# Sch_Add.net
KiCad netlist of a schematic drawn in Altium Designer
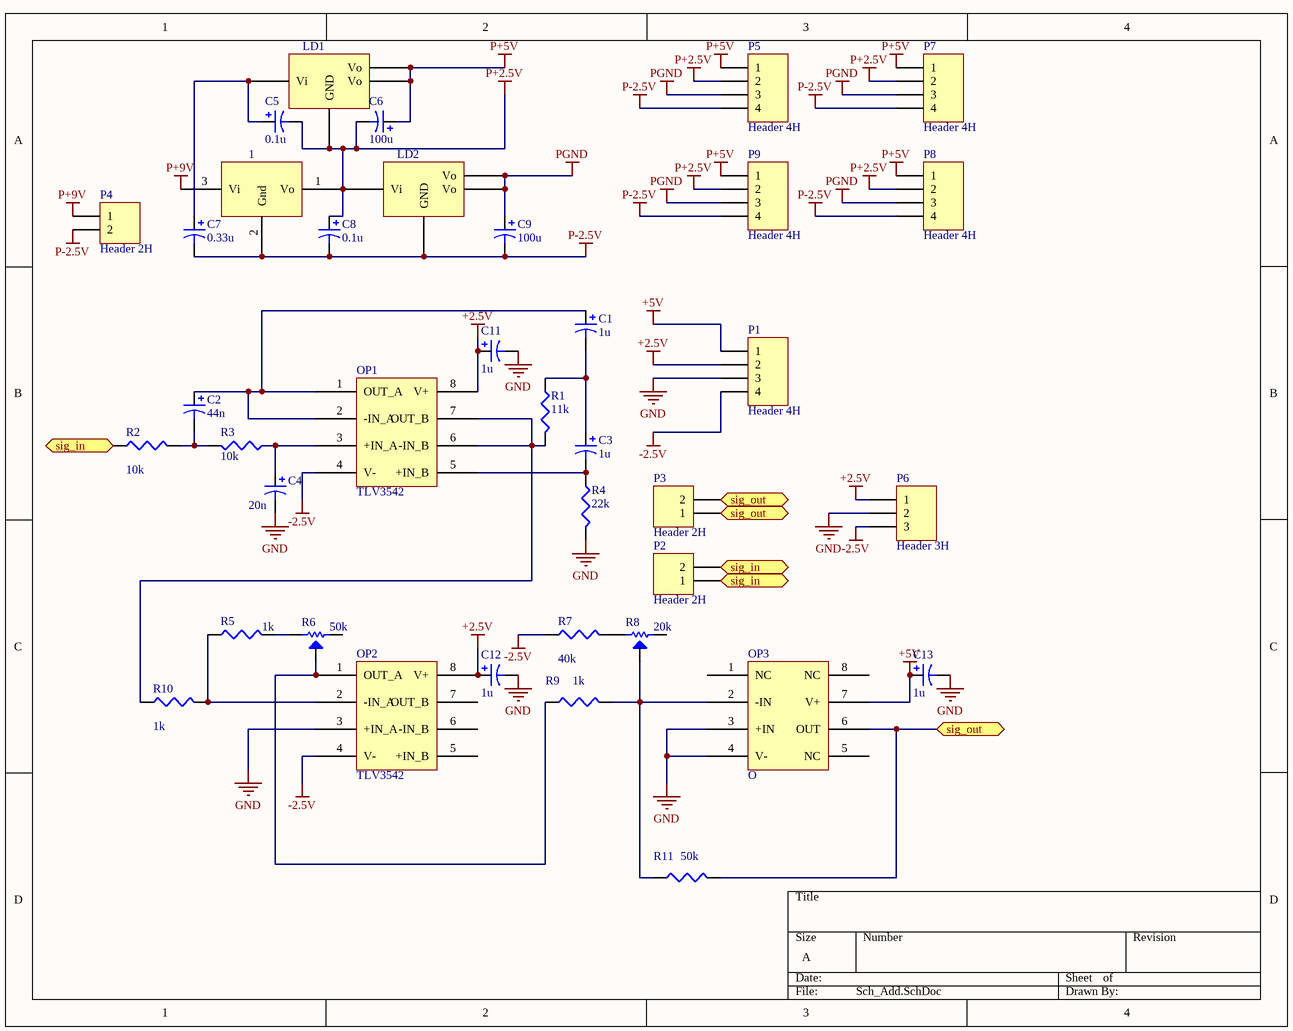
[diagram p0: Sch_Add.SchDoc]

(export (version "E")
  (design (tool "Eeschema 10.0.6"))
  (components
    (comp (ref "1") (value "7805") (footprint "TO-92") (libsource (lib "tlv3542") (part "7805")))
    (comp (ref "C1")
      (value "1u")
      (footprint "C0805")
      (description "Polarized Capacitor (Surface Mount)")
      (fields (field (name "Comment") "Cap Pol3") (field (name "PUBLISHER") "Altium Limited"))
      (libsource (lib "Miscellaneous Devices") (part "Cap Pol3"))
    )
    (comp (ref "C2")
      (value "44n")
      (footprint "C0805")
      (description "Polarized Capacitor (Surface Mount)")
      (fields (field (name "Comment") "Cap Pol3") (field (name "PUBLISHER") "Altium Limited"))
      (libsource (lib "Miscellaneous Devices") (part "Cap Pol3"))
    )
    (comp (ref "C3")
      (value "1u")
      (footprint "C0805")
      (description "Polarized Capacitor (Surface Mount)")
      (fields (field (name "Comment") "Cap Pol3") (field (name "PUBLISHER") "Altium Limited"))
      (libsource (lib "Miscellaneous Devices") (part "Cap Pol3"))
    )
    (comp (ref "C4")
      (value "20n")
      (footprint "C0805")
      (description "Polarized Capacitor (Surface Mount)")
      (fields (field (name "Comment") "Cap Pol3") (field (name "PUBLISHER") "Altium Limited"))
      (libsource (lib "Miscellaneous Devices") (part "Cap Pol3"))
    )
    (comp (ref "C5")
      (value "0.1u")
      (footprint "C0805")
      (description "Polarized Capacitor (Surface Mount)")
      (fields (field (name "Comment") "Cap Pol3") (field (name "PUBLISHER") "Altium Limited"))
      (libsource (lib "Miscellaneous Devices") (part "Cap Pol3"))
    )
    (comp (ref "C6")
      (value "100u")
      (footprint "C0805")
      (description "Polarized Capacitor (Surface Mount)")
      (fields (field (name "Comment") "Cap Pol3") (field (name "PUBLISHER") "Altium Limited"))
      (libsource (lib "Miscellaneous Devices") (part "Cap Pol3"))
    )
    (comp (ref "C7")
      (value "0.33u")
      (footprint "C0805")
      (description "Polarized Capacitor (Surface Mount)")
      (fields (field (name "Comment") "Cap Pol3") (field (name "PUBLISHER") "Altium Limited"))
      (libsource (lib "Miscellaneous Devices") (part "Cap Pol3"))
    )
    (comp (ref "C8")
      (value "0.1u")
      (footprint "C0805")
      (description "Polarized Capacitor (Surface Mount)")
      (fields (field (name "Comment") "Cap Pol3") (field (name "PUBLISHER") "Altium Limited"))
      (libsource (lib "Miscellaneous Devices") (part "Cap Pol3"))
    )
    (comp (ref "C9")
      (value "100u")
      (footprint "C0805")
      (description "Polarized Capacitor (Surface Mount)")
      (fields (field (name "Comment") "Cap Pol3") (field (name "PUBLISHER") "Altium Limited"))
      (libsource (lib "Miscellaneous Devices") (part "Cap Pol3"))
    )
    (comp (ref "C11")
      (value "1u")
      (footprint "C0805")
      (description "Polarized Capacitor (Surface Mount)")
      (fields (field (name "Comment") "Cap Pol3") (field (name "PUBLISHER") "Altium Limited"))
      (libsource (lib "Miscellaneous Devices") (part "Cap Pol3"))
    )
    (comp (ref "C12")
      (value "1u")
      (footprint "C0805")
      (description "Polarized Capacitor (Surface Mount)")
      (fields (field (name "Comment") "Cap Pol3") (field (name "PUBLISHER") "Altium Limited"))
      (libsource (lib "Miscellaneous Devices") (part "Cap Pol3"))
    )
    (comp (ref "C13")
      (value "1u")
      (footprint "C0805")
      (description "Polarized Capacitor (Surface Mount)")
      (fields (field (name "Comment") "Cap Pol3") (field (name "PUBLISHER") "Altium Limited"))
      (libsource (lib "Miscellaneous Devices") (part "Cap Pol3"))
    )
    (comp (ref "LD1")
      (value "LD1117")
      (footprint "SOT230P700X180-4N")
      (libsource (lib "tlv3542") (part "LD1117"))
    )
    (comp (ref "LD2")
      (value "LD1117")
      (footprint "SOT230P700X180-4N")
      (libsource (lib "tlv3542") (part "LD1117"))
    )
    (comp (ref "OP1")
      (value "TLV3542")
      (footprint "SOIC127P600X175-8N")
      (libsource (lib "tlv3542") (part "TLV3542"))
    )
    (comp (ref "OP2")
      (value "TLV3542")
      (footprint "SOIC127P600X175-8N")
      (libsource (lib "tlv3542") (part "TLV3542"))
    )
    (comp (ref "OP3")
      (value "O")
      (footprint "SOIC127P600X175-8N")
      (libsource (lib "tlv3542") (part "OPA388IDR"))
    )
    (comp (ref "P1")
      (value "Header 4H")
      (footprint "HDR1X4H")
      (description "Header, 4-Pin, Right Angle")
      (fields (field (name "PUBLISHER") "Altium Limited"))
      (libsource (lib "Miscellaneous Connectors") (part "Header 4H"))
    )
    (comp (ref "P2")
      (value "Header 2H")
      (footprint "HDR1X2H")
      (description "Header, 2-Pin, Right Angle")
      (fields (field (name "PUBLISHER") "Altium Limited"))
      (libsource (lib "Miscellaneous Connectors") (part "Header 2H"))
    )
    (comp (ref "P3")
      (value "Header 2H")
      (footprint "HDR1X2H")
      (description "Header, 2-Pin, Right Angle")
      (fields (field (name "PUBLISHER") "Altium Limited"))
      (libsource (lib "Miscellaneous Connectors") (part "Header 2H"))
    )
    (comp (ref "P4")
      (value "Header 2H")
      (footprint "HDR1X2H")
      (description "Header, 2-Pin, Right Angle")
      (fields (field (name "PUBLISHER") "Altium Limited"))
      (libsource (lib "") (part "Header 2H_1"))
    )
    (comp (ref "P5")
      (value "Header 4H")
      (footprint "HDR1X4H")
      (description "Header, 4-Pin, Right Angle")
      (fields (field (name "PUBLISHER") "Altium Limited"))
      (libsource (lib "Miscellaneous Connectors") (part "Header 4H"))
    )
    (comp (ref "P6")
      (value "Header 3H")
      (footprint "HDR1X3H")
      (description "Header, 3-Pin, Right Angle")
      (fields (field (name "PUBLISHER") "Altium Limited"))
      (libsource (lib "Miscellaneous Connectors") (part "Header 3H"))
    )
    (comp (ref "P7")
      (value "Header 4H")
      (footprint "HDR1X4H")
      (description "Header, 4-Pin, Right Angle")
      (fields (field (name "PUBLISHER") "Altium Limited"))
      (libsource (lib "Miscellaneous Connectors") (part "Header 4H"))
    )
    (comp (ref "P8")
      (value "Header 4H")
      (footprint "HDR1X4H")
      (description "Header, 4-Pin, Right Angle")
      (fields (field (name "PUBLISHER") "Altium Limited"))
      (libsource (lib "Miscellaneous Connectors") (part "Header 4H"))
    )
    (comp (ref "P9")
      (value "Header 4H")
      (footprint "HDR1X4H")
      (description "Header, 4-Pin, Right Angle")
      (fields (field (name "PUBLISHER") "Altium Limited"))
      (libsource (lib "Miscellaneous Connectors") (part "Header 4H"))
    )
    (comp (ref "R1")
      (value "11k")
      (footprint "J1-0603")
      (description "Resistor")
      (fields (field (name "Comment") "Res3") (field (name "PUBLISHER") "Altium Limited"))
      (libsource (lib "Miscellaneous Devices") (part "Res3"))
    )
    (comp (ref "R2")
      (value "10k")
      (footprint "J1-0603")
      (description "Resistor")
      (fields (field (name "Comment") "Res3") (field (name "PUBLISHER") "Altium Limited"))
      (libsource (lib "Miscellaneous Devices") (part "Res3"))
    )
    (comp (ref "R3")
      (value "10k")
      (footprint "J1-0603")
      (description "Resistor")
      (fields (field (name "Comment") "Res3") (field (name "PUBLISHER") "Altium Limited"))
      (libsource (lib "Miscellaneous Devices") (part "Res3"))
    )
    (comp (ref "R4")
      (value "22k")
      (footprint "J1-0603")
      (description "Resistor")
      (fields (field (name "Comment") "Res3") (field (name "PUBLISHER") "Altium Limited"))
      (libsource (lib "Miscellaneous Devices") (part "Res3"))
    )
    (comp (ref "R5")
      (value "1k")
      (footprint "J1-0603")
      (description "Resistor")
      (fields (field (name "Comment") "Res3") (field (name "PUBLISHER") "Altium Limited"))
      (libsource (lib "Miscellaneous Devices") (part "Res3"))
    )
    (comp (ref "R6")
      (value "50k")
      (footprint "3362P")
      (fields (field (name "Comment") "5"))
      (libsource (lib "tlv3542") (part "Res_3362P"))
    )
    (comp (ref "R7")
      (value "40k")
      (footprint "J1-0603")
      (description "Resistor")
      (fields (field (name "Comment") "Res3") (field (name "PUBLISHER") "Altium Limited"))
      (libsource (lib "Miscellaneous Devices") (part "Res3"))
    )
    (comp (ref "R8")
      (value "20k")
      (footprint "3362P")
      (fields (field (name "Comment") "2"))
      (libsource (lib "tlv3542") (part "Res_3362P"))
    )
    (comp (ref "R9")
      (value "1k")
      (footprint "J1-0603")
      (description "Resistor")
      (fields (field (name "Comment") "Res3") (field (name "PUBLISHER") "Altium Limited"))
      (libsource (lib "Miscellaneous Devices") (part "Res3"))
    )
    (comp (ref "R10")
      (value "1k")
      (footprint "J1-0603")
      (description "Resistor")
      (fields (field (name "Comment") "Res3") (field (name "PUBLISHER") "Altium Limited"))
      (libsource (lib "Miscellaneous Devices") (part "Res3"))
    )
    (comp (ref "R11")
      (value "50k")
      (footprint "J1-0603")
      (description "Resistor")
      (fields (field (name "Comment") "Res3") (field (name "PUBLISHER") "Altium Limited"))
      (libsource (lib "Miscellaneous Devices") (part "Res3"))
    )
  )
  (nets
    (net (code "1") (name "+2.5V") (class "Default")
      (node (ref "C11") (pin "1") (pinfunction "1_1") (pintype "passive"))
      (node (ref "C12") (pin "1") (pinfunction "1_1") (pintype "passive"))
      (node (ref "OP1") (pin "8") (pinfunction "V+_8") (pintype "passive"))
      (node (ref "OP2") (pin "8") (pinfunction "V+_8") (pintype "passive"))
      (node (ref "P1") (pin "2") (pinfunction "2_2") (pintype "passive"))
      (node (ref "P6") (pin "1") (pinfunction "1_1") (pintype "passive"))
    )
    (net (code "2") (name "+5V") (class "Default")
      (node (ref "C13") (pin "1") (pinfunction "1_1") (pintype "passive"))
      (node (ref "OP3") (pin "7") (pinfunction "V+_7") (pintype "passive"))
      (node (ref "P1") (pin "1") (pinfunction "1_1") (pintype "passive"))
    )
    (net (code "3") (name "-2.5V") (class "Default")
      (node (ref "OP1") (pin "4") (pinfunction "V-_4") (pintype "passive"))
      (node (ref "OP2") (pin "4") (pinfunction "V-_4") (pintype "passive"))
      (node (ref "P1") (pin "4") (pinfunction "4_4") (pintype "passive"))
      (node (ref "P6") (pin "3") (pinfunction "3_3") (pintype "passive"))
      (node (ref "R7") (pin "1") (pinfunction "1_1") (pintype "passive"))
    )
    (net (code "4") (name "/sig_in") (class "Default")
      (node (ref "P2") (pin "1") (pinfunction "1_1") (pintype "passive"))
      (node (ref "P2") (pin "2") (pinfunction "2_2") (pintype "passive"))
      (node (ref "R2") (pin "1") (pinfunction "1_1") (pintype "passive"))
    )
    (net (code "5") (name "/sig_out") (class "Default")
      (node (ref "OP3") (pin "6") (pinfunction "OUT_6") (pintype "passive"))
      (node (ref "P3") (pin "1") (pinfunction "1_1") (pintype "passive"))
      (node (ref "P3") (pin "2") (pinfunction "2_2") (pintype "passive"))
      (node (ref "R11") (pin "2") (pinfunction "2_2") (pintype "passive"))
    )
    (net (code "6") (name "GND") (class "Default")
      (node (ref "C11") (pin "2") (pinfunction "2_2") (pintype "passive"))
      (node (ref "C12") (pin "2") (pinfunction "2_2") (pintype "passive"))
      (node (ref "C13") (pin "2") (pinfunction "2_2") (pintype "passive"))
      (node (ref "C4") (pin "2") (pinfunction "2_2") (pintype "passive"))
      (node (ref "OP2") (pin "3") (pinfunction "+IN_A_3") (pintype "passive"))
      (node (ref "OP3") (pin "3") (pinfunction "+IN_3") (pintype "passive"))
      (node (ref "OP3") (pin "4") (pinfunction "V-_4") (pintype "passive"))
      (node (ref "P1") (pin "3") (pinfunction "3_3") (pintype "passive"))
      (node (ref "P6") (pin "2") (pinfunction "2_2") (pintype "passive"))
      (node (ref "R4") (pin "2") (pinfunction "2_2") (pintype "passive"))
    )
    (net (code "7") (name "Net-(C1-Pad2)") (class "Default")
      (node (ref "C1") (pin "2") (pinfunction "2_2") (pintype "passive"))
      (node (ref "C3") (pin "1") (pinfunction "1_1") (pintype "passive"))
      (node (ref "R1") (pin "1") (pinfunction "1_1") (pintype "passive"))
    )
    (net (code "8") (name "Net-(C2-Pad2)") (class "Default")
      (node (ref "C2") (pin "2") (pinfunction "2_2") (pintype "passive"))
      (node (ref "R2") (pin "2") (pinfunction "2_2") (pintype "passive"))
      (node (ref "R3") (pin "2") (pinfunction "2_2") (pintype "passive"))
    )
    (net (code "9") (name "Net-(LD1-Vi)") (class "Default")
      (node (ref "C5") (pin "1") (pinfunction "1_1") (pintype "passive"))
      (node (ref "C7") (pin "1") (pinfunction "1_1") (pintype "passive"))
      (node (ref "LD1") (pin "3") (pinfunction "Vi_3") (pintype "passive"))
    )
    (net (code "10") (name "Net-(OP1-+IN_A)") (class "Default")
      (node (ref "C4") (pin "1") (pinfunction "1_1") (pintype "passive"))
      (node (ref "OP1") (pin "3") (pinfunction "+IN_A_3") (pintype "passive"))
      (node (ref "R3") (pin "1") (pinfunction "1_1") (pintype "passive"))
    )
    (net (code "11") (name "Net-(OP1-+IN_B)") (class "Default")
      (node (ref "C3") (pin "2") (pinfunction "2_2") (pintype "passive"))
      (node (ref "OP1") (pin "5") (pinfunction "+IN_B_5") (pintype "passive"))
      (node (ref "R4") (pin "1") (pinfunction "1_1") (pintype "passive"))
    )
    (net (code "12") (name "Net-(OP1--IN_A)") (class "Default")
      (node (ref "C1") (pin "1") (pinfunction "1_1") (pintype "passive"))
      (node (ref "C2") (pin "1") (pinfunction "1_1") (pintype "passive"))
      (node (ref "OP1") (pin "1") (pinfunction "OUT_A_1") (pintype "passive"))
      (node (ref "OP1") (pin "2") (pinfunction "-IN_A_2") (pintype "passive"))
    )
    (net (code "13") (name "Net-(OP1--IN_B)") (class "Default")
      (node (ref "OP1") (pin "6") (pinfunction "-IN_B_6") (pintype "passive"))
      (node (ref "OP1") (pin "7") (pinfunction "OUT_B_7") (pintype "passive"))
      (node (ref "R1") (pin "2") (pinfunction "2_2") (pintype "passive"))
      (node (ref "R10") (pin "1") (pinfunction "1_1") (pintype "passive"))
    )
    (net (code "14") (name "Net-(OP2--IN_A)") (class "Default")
      (node (ref "OP2") (pin "2") (pinfunction "-IN_A_2") (pintype "passive"))
      (node (ref "R10") (pin "2") (pinfunction "2_2") (pintype "passive"))
      (node (ref "R5") (pin "1") (pinfunction "1_1") (pintype "passive"))
    )
    (net (code "15") (name "Net-(OP2-OUT_A)") (class "Default")
      (node (ref "OP2") (pin "1") (pinfunction "OUT_A_1") (pintype "passive"))
      (node (ref "R6") (pin "3") (pinfunction "3_3") (pintype "passive"))
      (node (ref "R9") (pin "1") (pinfunction "1_1") (pintype "passive"))
    )
    (net (code "16") (name "Net-(OP3--IN)") (class "Default")
      (node (ref "OP3") (pin "2") (pinfunction "-IN_2") (pintype "passive"))
      (node (ref "R11") (pin "1") (pinfunction "1_1") (pintype "passive"))
      (node (ref "R8") (pin "3") (pinfunction "3_3") (pintype "passive"))
      (node (ref "R9") (pin "2") (pinfunction "2_2") (pintype "passive"))
    )
    (net (code "17") (name "Net-(R5-Pad2)") (class "Default")
      (node (ref "R5") (pin "2") (pinfunction "2_2") (pintype "passive"))
      (node (ref "R6") (pin "1") (pinfunction "1_1") (pintype "passive"))
    )
    (net (code "18") (name "Net-(R7-Pad2)") (class "Default")
      (node (ref "R7") (pin "2") (pinfunction "2_2") (pintype "passive"))
      (node (ref "R8") (pin "1") (pinfunction "1_1") (pintype "passive"))
    )
    (net (code "19") (name "P+2.5V") (class "Default")
      (node (ref "1") (pin "1") (pinfunction "Vo_1") (pintype "passive"))
      (node (ref "C5") (pin "2") (pinfunction "2_2") (pintype "passive"))
      (node (ref "C6") (pin "2") (pinfunction "2_2") (pintype "passive"))
      (node (ref "C8") (pin "1") (pinfunction "1_1") (pintype "passive"))
      (node (ref "LD1") (pin "1") (pinfunction "GND_1") (pintype "passive"))
      (node (ref "LD2") (pin "3") (pinfunction "Vi_3") (pintype "passive"))
      (node (ref "P5") (pin "2") (pinfunction "2_2") (pintype "passive"))
      (node (ref "P7") (pin "2") (pinfunction "2_2") (pintype "passive"))
      (node (ref "P8") (pin "2") (pinfunction "2_2") (pintype "passive"))
      (node (ref "P9") (pin "2") (pinfunction "2_2") (pintype "passive"))
    )
    (net (code "20") (name "P+5V") (class "Default")
      (node (ref "C6") (pin "1") (pinfunction "1_1") (pintype "passive"))
      (node (ref "LD1") (pin "2") (pinfunction "Vo_2") (pintype "passive"))
      (node (ref "LD1") (pin "4") (pinfunction "Vo_4") (pintype "passive"))
      (node (ref "P5") (pin "1") (pinfunction "1_1") (pintype "passive"))
      (node (ref "P7") (pin "1") (pinfunction "1_1") (pintype "passive"))
      (node (ref "P8") (pin "1") (pinfunction "1_1") (pintype "passive"))
      (node (ref "P9") (pin "1") (pinfunction "1_1") (pintype "passive"))
    )
    (net (code "21") (name "P+9V") (class "Default")
      (node (ref "1") (pin "3") (pinfunction "Vi_3") (pintype "passive"))
      (node (ref "P4") (pin "1") (pinfunction "1_1") (pintype "passive"))
    )
    (net (code "22") (name "P-2.5V") (class "Default")
      (node (ref "1") (pin "2") (pinfunction "Gnd_2") (pintype "passive"))
      (node (ref "C7") (pin "2") (pinfunction "2_2") (pintype "passive"))
      (node (ref "C8") (pin "2") (pinfunction "2_2") (pintype "passive"))
      (node (ref "C9") (pin "2") (pinfunction "2_2") (pintype "passive"))
      (node (ref "LD2") (pin "1") (pinfunction "GND_1") (pintype "passive"))
      (node (ref "P4") (pin "2") (pinfunction "2_2") (pintype "passive"))
      (node (ref "P5") (pin "4") (pinfunction "4_4") (pintype "passive"))
      (node (ref "P7") (pin "4") (pinfunction "4_4") (pintype "passive"))
      (node (ref "P8") (pin "4") (pinfunction "4_4") (pintype "passive"))
      (node (ref "P9") (pin "4") (pinfunction "4_4") (pintype "passive"))
    )
    (net (code "23") (name "PGND") (class "Default")
      (node (ref "C9") (pin "1") (pinfunction "1_1") (pintype "passive"))
      (node (ref "LD2") (pin "2") (pinfunction "Vo_2") (pintype "passive"))
      (node (ref "LD2") (pin "4") (pinfunction "Vo_4") (pintype "passive"))
      (node (ref "P5") (pin "3") (pinfunction "3_3") (pintype "passive"))
      (node (ref "P7") (pin "3") (pinfunction "3_3") (pintype "passive"))
      (node (ref "P8") (pin "3") (pinfunction "3_3") (pintype "passive"))
      (node (ref "P9") (pin "3") (pinfunction "3_3") (pintype "passive"))
    )
    (net (code "24") (name "unconnected-(OP2-+IN_B-Pad5)") (class "Default")
      (node (ref "OP2") (pin "5") (pinfunction "+IN_B_5") (pintype "passive"))
    )
    (net (code "25") (name "unconnected-(OP2--IN_B-Pad6)") (class "Default")
      (node (ref "OP2") (pin "6") (pinfunction "-IN_B_6") (pintype "passive"))
    )
    (net (code "26") (name "unconnected-(OP2-OUT_B-Pad7)") (class "Default")
      (node (ref "OP2") (pin "7") (pinfunction "OUT_B_7") (pintype "passive"))
    )
    (net (code "27") (name "unconnected-(OP3-NC-Pad1)") (class "Default")
      (node (ref "OP3") (pin "1") (pinfunction "NC_1") (pintype "passive"))
    )
    (net (code "28") (name "unconnected-(OP3-NC-Pad5)") (class "Default")
      (node (ref "OP3") (pin "5") (pinfunction "NC_5") (pintype "passive"))
    )
    (net (code "29") (name "unconnected-(OP3-NC-Pad8)") (class "Default")
      (node (ref "OP3") (pin "8") (pinfunction "NC_8") (pintype "passive"))
    )
    (net (code "30") (name "unconnected-(R6-Pad2)") (class "Default")
      (node (ref "R6") (pin "2") (pinfunction "2_2") (pintype "passive"))
    )
    (net (code "31") (name "unconnected-(R8-Pad2)") (class "Default")
      (node (ref "R8") (pin "2") (pinfunction "2_2") (pintype "passive"))
    )
  )
)
